# 10_MISC.net
KiCad netlist of a schematic drawn in Altium Designer
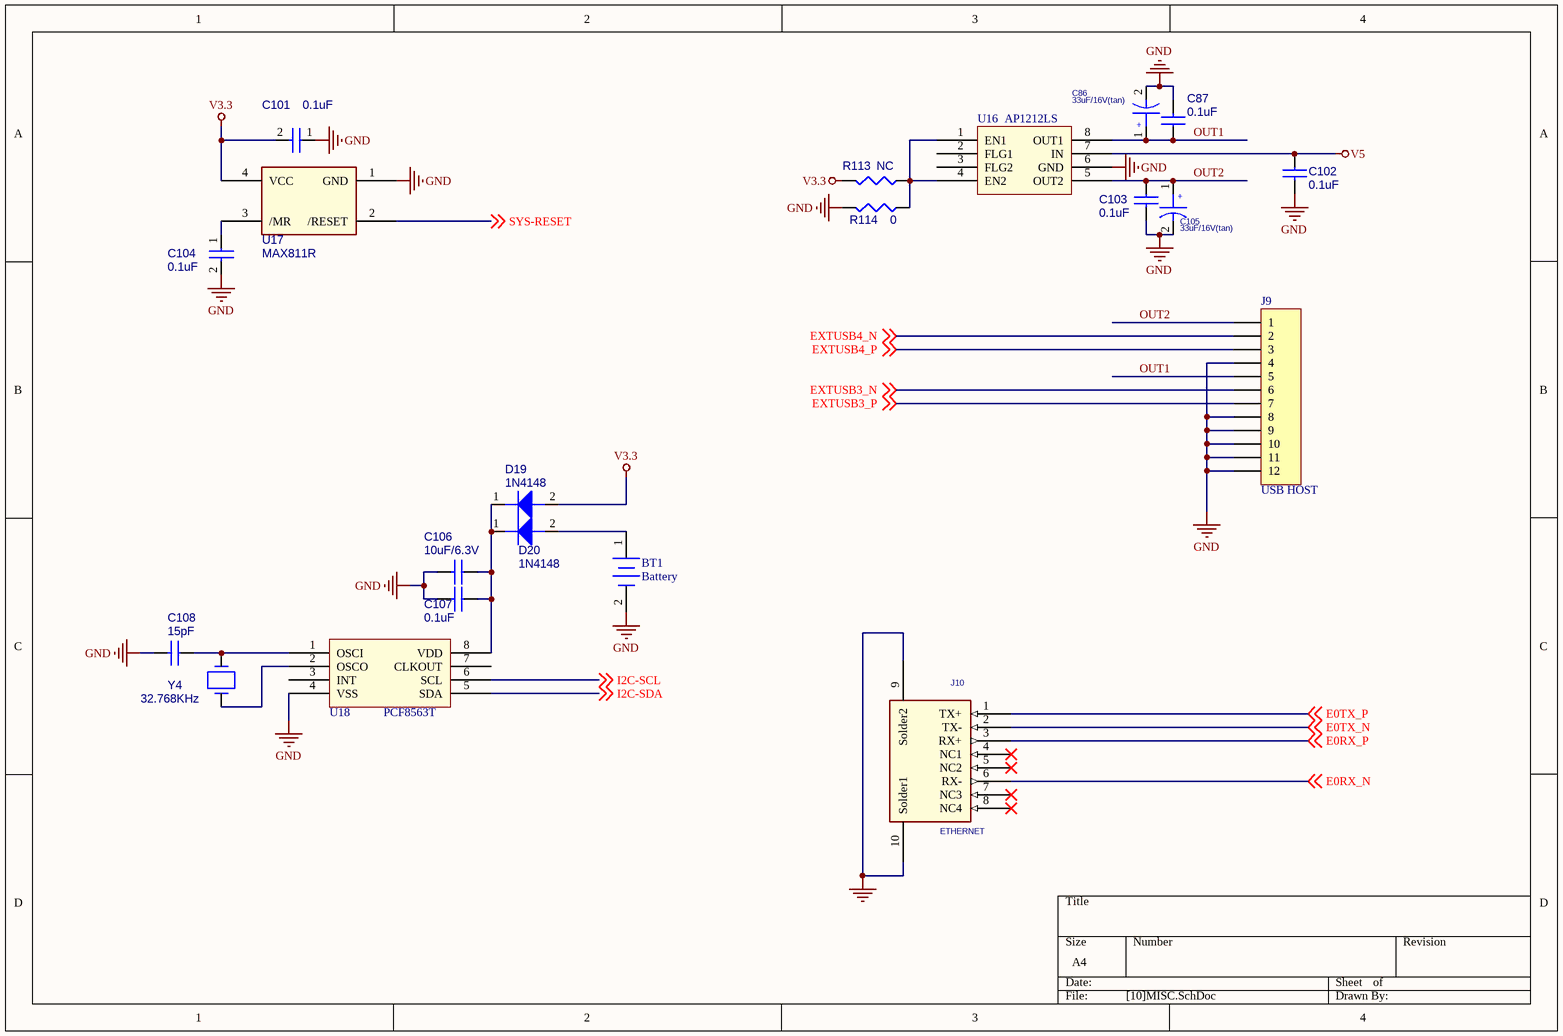
[diagram p0: [10]MISC.SchDoc]

(export (version "E")
  (design (tool "Eeschema 10.0.6"))
  (components
    (comp (ref "BT1")
      (value "Battery")
      (footprint "CR1220")
      (description "Multicell Battery")
      (libsource (lib "Miscellaneous Devices") (part "Battery"))
    )
    (comp (ref "C86") (value "33uF/16V(tan)") (footprint "3528") (libsource (lib "*") (part "CAP WP")))
    (comp (ref "C87") (value "0.1uF") (libsource (lib "*") (part "CAP_Dup1")))
    (comp (ref "C101") (value "0.1uF") (libsource (lib "*") (part "CAP NP_Dup2")))
    (comp (ref "C102") (value "0.1uF") (libsource (lib "*") (part "CAP_Dup1")))
    (comp (ref "C103") (value "0.1uF") (libsource (lib "*") (part "CAP_Dup1")))
    (comp (ref "C104") (value "0.1uF") (libsource (lib "*") (part "CAP NP_Dup2")))
    (comp (ref "C105") (value "33uF/16V(tan)") (footprint "3528") (libsource (lib "*") (part "CAP WP")))
    (comp (ref "C106") (value "10uF/6.3V") (footprint "0805") (libsource (lib "*") (part "CAP_Dup1")))
    (comp (ref "C107") (value "0.1uF") (libsource (lib "*") (part "CAP_Dup1")))
    (comp (ref "C108") (value "15pF") (libsource (lib "*") (part "CAP_Dup1")))
    (comp (ref "D19")
      (value "1N4148")
      (footprint "MINI-MELF")
      (libsource (lib "*") (part "1N4148WS-7-F_SOD323-2"))
    )
    (comp (ref "D20")
      (value "1N4148")
      (footprint "MINI-MELF")
      (libsource (lib "*") (part "1N4148WS-7-F_SOD323-2"))
    )
    (comp (ref "J9")
      (value "USB HOST")
      (footprint "USB-HOST-2")
      (description "Header, 12-Pin")
      (fields (field (name "PUBLISHER") "Altium Limited"))
      (libsource (lib "Miscellaneous Connectors") (part "Header 12"))
    )
    (comp (ref "J10") (value "ETHERNET") (libsource (lib "*") (part "NET")))
    (comp (ref "R113")
      (value "NC")
      (fields (field (name "PART NUMBER") "SD02810028L"))
      (libsource (lib "*") (part "R"))
    )
    (comp (ref "R114")
      (value "0")
      (fields (field (name "PART NUMBER") "SD02810028L"))
      (libsource (lib "*") (part "R"))
    )
    (comp (ref "U16") (value "AP1212LS") (footprint "SO8") (libsource (lib "Schlib") (part "AP1212")))
    (comp (ref "U17") (value "MAX811R") (libsource (lib "*") (part "MAX811")))
    (comp (ref "U18") (value "PCF8563T") (footprint "SO8") (libsource (lib "Schlib") (part "PCF8563T")))
    (comp (ref "Y4") (value "32.768KHz") (libsource (lib "*") (part "CRYSTAL")))
  )
  (nets
    (net (code "1") (name "/OUT1") (class "Default")
      (node (ref "C86") (pin "1") (pinfunction "1_1") (pintype "passive"))
      (node (ref "C87") (pin "1") (pinfunction "1_1") (pintype "passive"))
      (node (ref "J9") (pin "5") (pinfunction "5_5") (pintype "passive"))
      (node (ref "U16") (pin "8") (pinfunction "OUT1_8") (pintype "passive"))
    )
    (net (code "2") (name "/OUT2") (class "Default")
      (node (ref "C103") (pin "1") (pinfunction "1_1") (pintype "passive"))
      (node (ref "C105") (pin "1") (pinfunction "1_1") (pintype "passive"))
      (node (ref "J9") (pin "1") (pinfunction "1_1") (pintype "passive"))
      (node (ref "U16") (pin "5") (pinfunction "OUT2_5") (pintype "passive"))
    )
    (net (code "3") (name "E0RX_N") (class "Default")
      (node (ref "J10") (pin "6") (pinfunction "RX-_6") (pintype "output"))
    )
    (net (code "4") (name "E0RX_P") (class "Default")
      (node (ref "J10") (pin "3") (pinfunction "RX+_3") (pintype "output"))
    )
    (net (code "5") (name "E0TX_N") (class "Default")
      (node (ref "J10") (pin "2") (pinfunction "TX-_2") (pintype "input"))
    )
    (net (code "6") (name "E0TX_P") (class "Default")
      (node (ref "J10") (pin "1") (pinfunction "TX+_1") (pintype "input"))
    )
    (net (code "7") (name "EXTUSB3_N") (class "Default")
      (node (ref "J9") (pin "6") (pinfunction "6_6") (pintype "passive"))
    )
    (net (code "8") (name "EXTUSB3_P") (class "Default")
      (node (ref "J9") (pin "7") (pinfunction "7_7") (pintype "passive"))
    )
    (net (code "9") (name "EXTUSB4_N") (class "Default")
      (node (ref "J9") (pin "2") (pinfunction "2_2") (pintype "passive"))
    )
    (net (code "10") (name "EXTUSB4_P") (class "Default")
      (node (ref "J9") (pin "3") (pinfunction "3_3") (pintype "passive"))
    )
    (net (code "11") (name "GND") (class "Default")
      (node (ref "BT1") (pin "2") (pinfunction "-_2") (pintype "passive"))
      (node (ref "C101") (pin "1") (pinfunction "1_1") (pintype "passive"))
      (node (ref "C102") (pin "2") (pinfunction "2_2") (pintype "passive"))
      (node (ref "C103") (pin "2") (pinfunction "2_2") (pintype "passive"))
      (node (ref "C104") (pin "2") (pinfunction "2_2") (pintype "passive"))
      (node (ref "C105") (pin "2") (pinfunction "2_2") (pintype "passive"))
      (node (ref "C106") (pin "2") (pinfunction "2_2") (pintype "passive"))
      (node (ref "C107") (pin "2") (pinfunction "2_2") (pintype "passive"))
      (node (ref "C108") (pin "2") (pinfunction "2_2") (pintype "passive"))
      (node (ref "C86") (pin "2") (pinfunction "2_2") (pintype "passive"))
      (node (ref "C87") (pin "2") (pinfunction "2_2") (pintype "passive"))
      (node (ref "J10") (pin "10") (pinfunction "Solder1_10") (pintype "passive"))
      (node (ref "J10") (pin "9") (pinfunction "Solder2_9") (pintype "passive"))
      (node (ref "J9") (pin "10") (pinfunction "10_10") (pintype "passive"))
      (node (ref "J9") (pin "11") (pinfunction "11_11") (pintype "passive"))
      (node (ref "J9") (pin "12") (pinfunction "12_12") (pintype "passive"))
      (node (ref "J9") (pin "4") (pinfunction "4_4") (pintype "passive"))
      (node (ref "J9") (pin "8") (pinfunction "8_8") (pintype "passive"))
      (node (ref "J9") (pin "9") (pinfunction "9_9") (pintype "passive"))
      (node (ref "R114") (pin "2") (pinfunction "2_2") (pintype "passive"))
      (node (ref "U16") (pin "6") (pinfunction "GND_6") (pintype "passive"))
      (node (ref "U17") (pin "1") (pinfunction "GND_1") (pintype "passive"))
      (node (ref "U18") (pin "4") (pinfunction "VSS_4") (pintype "passive"))
    )
    (net (code "12") (name "I2C-SCL") (class "Default")
      (node (ref "U18") (pin "6") (pinfunction "SCL_6") (pintype "passive"))
    )
    (net (code "13") (name "I2C-SDA") (class "Default")
      (node (ref "U18") (pin "5") (pinfunction "SDA_5") (pintype "passive"))
    )
    (net (code "14") (name "Net-(BT1-+)") (class "Default")
      (node (ref "BT1") (pin "1") (pinfunction "+_1") (pintype "passive"))
      (node (ref "D20") (pin "2") (pinfunction "2_2") (pintype "passive"))
    )
    (net (code "15") (name "Net-(U16-EN1)") (class "Default")
      (node (ref "R113") (pin "1") (pinfunction "1_1") (pintype "passive"))
      (node (ref "R114") (pin "1") (pinfunction "1_1") (pintype "passive"))
      (node (ref "U16") (pin "1") (pinfunction "EN1_1") (pintype "passive"))
      (node (ref "U16") (pin "4") (pinfunction "EN2_4") (pintype "passive"))
    )
    (net (code "16") (name "Net-(U17-{slash}MR)") (class "Default")
      (node (ref "C104") (pin "1") (pinfunction "1_1") (pintype "passive"))
      (node (ref "U17") (pin "3") (pinfunction "/MR_3") (pintype "passive"))
    )
    (net (code "17") (name "Net-(U18-OSCI)") (class "Default")
      (node (ref "C108") (pin "1") (pinfunction "1_1") (pintype "passive"))
      (node (ref "U18") (pin "1") (pinfunction "OSCI_1") (pintype "passive"))
      (node (ref "Y4") (pin "2") (pinfunction "2_2") (pintype "passive"))
    )
    (net (code "18") (name "Net-(U18-OSCO)") (class "Default")
      (node (ref "U18") (pin "2") (pinfunction "OSCO_2") (pintype "passive"))
      (node (ref "Y4") (pin "1") (pinfunction "1_1") (pintype "passive"))
    )
    (net (code "19") (name "Net-(U18-VDD)") (class "Default")
      (node (ref "C106") (pin "1") (pinfunction "1_1") (pintype "passive"))
      (node (ref "C107") (pin "1") (pinfunction "1_1") (pintype "passive"))
      (node (ref "D19") (pin "1") (pinfunction "1_1") (pintype "passive"))
      (node (ref "D20") (pin "1") (pinfunction "1_1") (pintype "passive"))
      (node (ref "U18") (pin "8") (pinfunction "VDD_8") (pintype "passive"))
    )
    (net (code "20") (name "SYS-RESET") (class "Default")
      (node (ref "U17") (pin "2") (pinfunction "/RESET_2") (pintype "passive"))
    )
    (net (code "21") (name "V3.3") (class "Default")
      (node (ref "C101") (pin "2") (pinfunction "2_2") (pintype "passive"))
      (node (ref "D19") (pin "2") (pinfunction "2_2") (pintype "passive"))
      (node (ref "R113") (pin "2") (pinfunction "2_2") (pintype "passive"))
      (node (ref "U17") (pin "4") (pinfunction "VCC_4") (pintype "passive"))
    )
    (net (code "22") (name "V5") (class "Default")
      (node (ref "C102") (pin "1") (pinfunction "1_1") (pintype "passive"))
      (node (ref "U16") (pin "7") (pinfunction "IN_7") (pintype "passive"))
    )
    (net (code "23") (name "unconnected-(J10-NC1-Pad4)") (class "Default")
      (node (ref "J10") (pin "4") (pinfunction "NC1_4") (pintype "input+no_connect"))
    )
    (net (code "24") (name "unconnected-(J10-NC2-Pad5)") (class "Default")
      (node (ref "J10") (pin "5") (pinfunction "NC2_5") (pintype "input+no_connect"))
    )
    (net (code "25") (name "unconnected-(J10-NC3-Pad7)") (class "Default")
      (node (ref "J10") (pin "7") (pinfunction "NC3_7") (pintype "input+no_connect"))
    )
    (net (code "26") (name "unconnected-(J10-NC4-Pad8)") (class "Default")
      (node (ref "J10") (pin "8") (pinfunction "NC4_8") (pintype "input+no_connect"))
    )
    (net (code "27") (name "unconnected-(U16-FLG1-Pad2)") (class "Default")
      (node (ref "U16") (pin "2") (pinfunction "FLG1_2") (pintype "passive"))
    )
    (net (code "28") (name "unconnected-(U16-FLG2-Pad3)") (class "Default")
      (node (ref "U16") (pin "3") (pinfunction "FLG2_3") (pintype "passive"))
    )
    (net (code "29") (name "unconnected-(U18-CLKOUT-Pad7)") (class "Default")
      (node (ref "U18") (pin "7") (pinfunction "CLKOUT_7") (pintype "passive"))
    )
    (net (code "30") (name "unconnected-(U18-INT-Pad3)") (class "Default")
      (node (ref "U18") (pin "3") (pinfunction "INT_3") (pintype "passive"))
    )
  )
)
